# Pico_40Pin_Keyboard.net
KiCad netlist of a schematic drawn in EAGLE
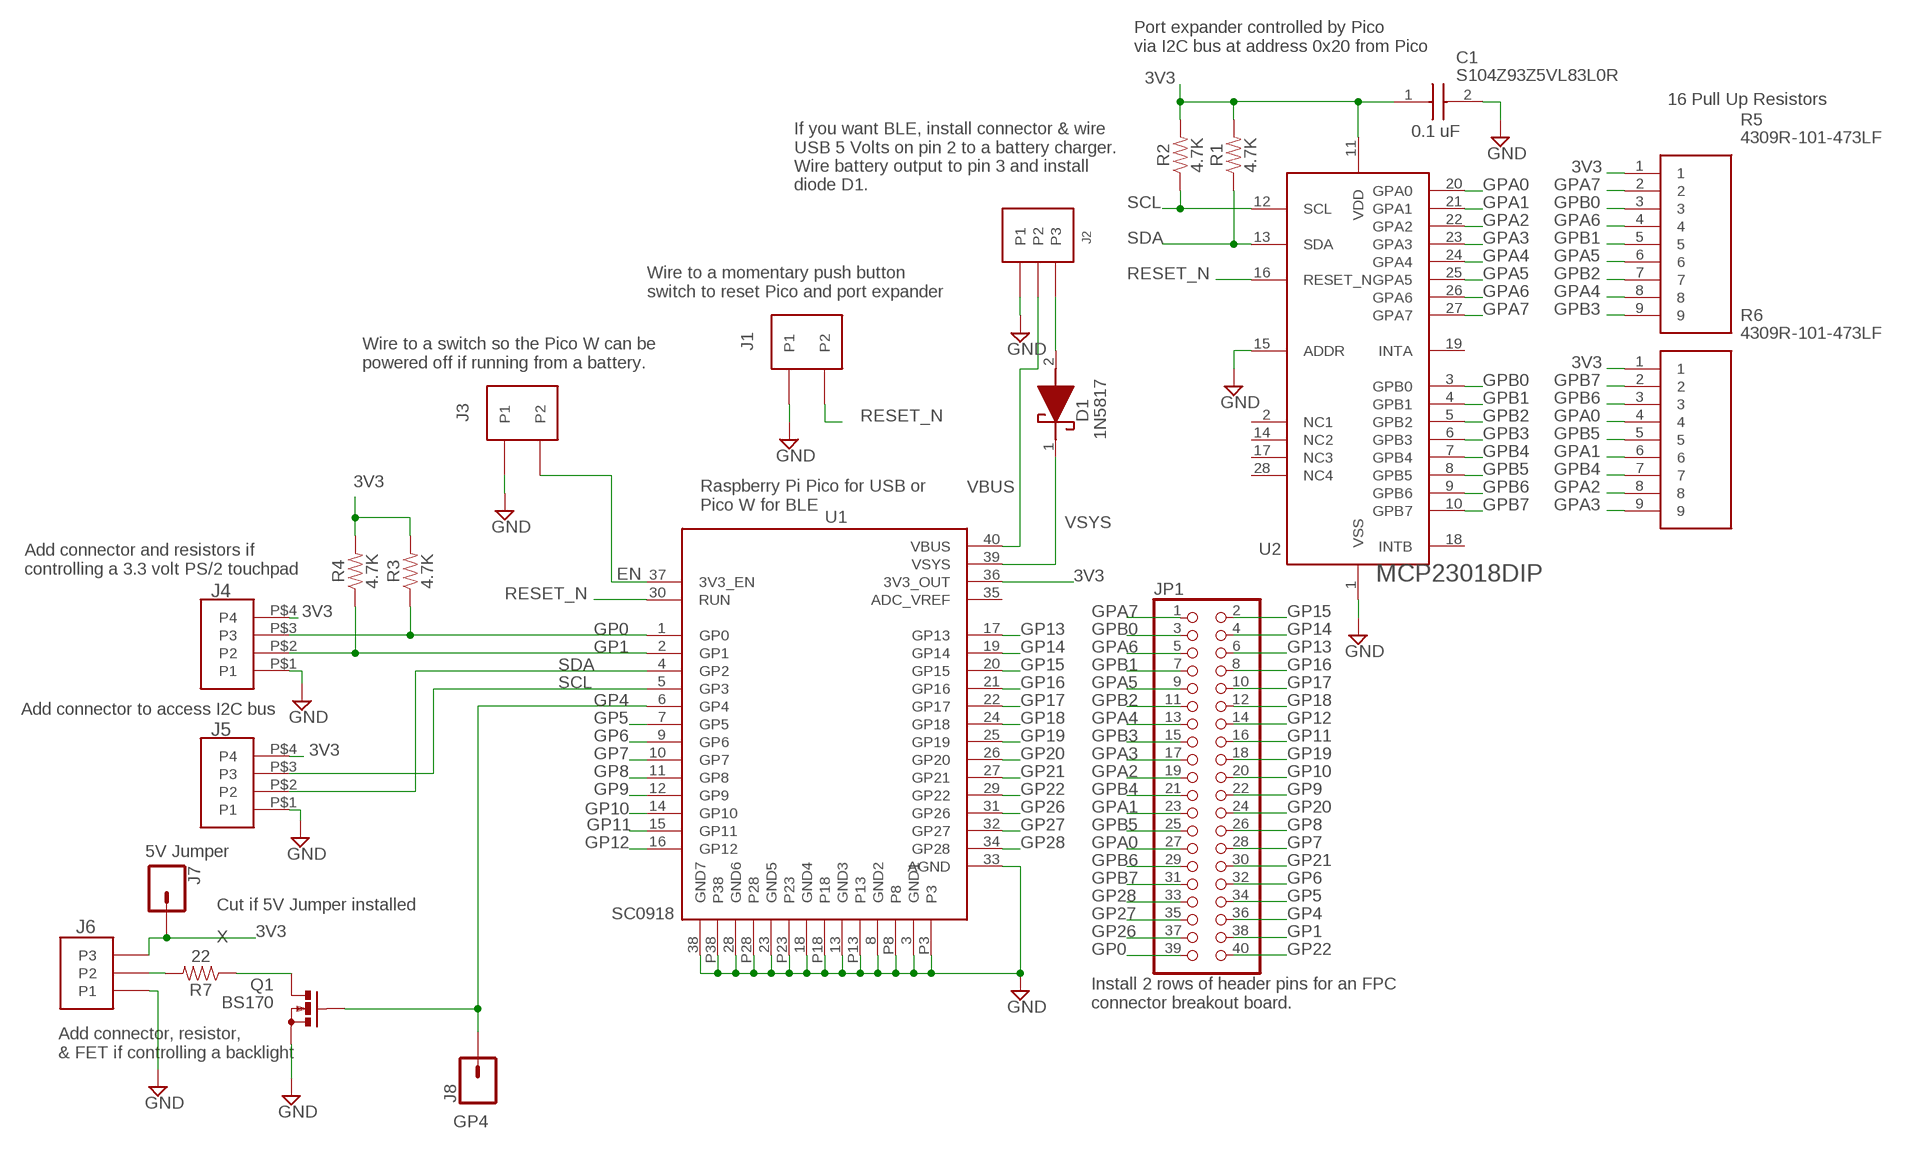
[diagram p0: schematic, sheet 1]

(export (version "E")
  (design (tool "Eeschema 10.0.6"))
  (components
    (comp (ref "C1")
      (value "S104Z93Z5VL83L0R")
      (footprint "eagle-import:S104Z93Z5VL83L0R")
      (fields (field (name "MOUSER_PART_NUMBER") "594-S104Z93Z5VL83L0R"))
      (libsource (lib "eagle-import") (part "S104Z93Z5VL83L0R"))
    )
    (comp (ref "D1")
      (value "1N5817")
      (footprint "eagle-import:DIOAD1410W86L470D235")
      (fields (field (name "MOUSER_PART_NUMBER") "821-1N5817"))
      (libsource (lib "eagle-import") (part "1N5817"))
    )
    (comp (ref "J1")
      (value "JST-PH-2PIN")
      (footprint "eagle-import:JST-PH-2PIN")
      (libsource (lib "eagle-import") (part "JST-PH-2PIN"))
    )
    (comp (ref "J2")
      (value "JST-PH-3PIN")
      (footprint "eagle-import:JST-PH-3PIN")
      (libsource (lib "eagle-import") (part "JST-PH-3PIN"))
    )
    (comp (ref "J3")
      (value "JST-PH-2PIN")
      (footprint "eagle-import:JST-PH-2PIN")
      (libsource (lib "eagle-import") (part "JST-PH-2PIN"))
    )
    (comp (ref "J4")
      (value "JST-PH-4PIN")
      (footprint "eagle-import:JST-PH-4PIN")
      (libsource (lib "eagle-import") (part "JST-PH-4PIN"))
    )
    (comp (ref "J5")
      (value "JST-PH-4PIN")
      (footprint "eagle-import:JST-PH-4PIN")
      (libsource (lib "eagle-import") (part "JST-PH-4PIN"))
    )
    (comp (ref "J6")
      (value "JST-PH-3PIN")
      (footprint "eagle-import:JST-PH-3PIN")
      (libsource (lib "eagle-import") (part "JST-PH-3PIN"))
    )
    (comp (ref "J7")
      (value "CONN_01")
      (footprint "eagle-import:1X01")
      (libsource (lib "eagle-import") (part "CONN_01"))
    )
    (comp (ref "J8")
      (value "CONN_01")
      (footprint "eagle-import:1X01")
      (libsource (lib "eagle-import") (part "CONN_01"))
    )
    (comp (ref "JP1")
      (value "PINHD-2X20")
      (footprint "eagle-import:2X20")
      (libsource (lib "eagle-import") (part "PINHD-2X20"))
    )
    (comp (ref "Q1")
      (value "BS170")
      (footprint "eagle-import:SOT54E")
      (libsource (lib "eagle-import") (part "BS170"))
    )
    (comp (ref "R1")
      (value "4.7K")
      (footprint "eagle-import:AXIAL-0.3")
      (libsource (lib "eagle-import") (part "RESISTOR_AXIAL"))
    )
    (comp (ref "R2")
      (value "4.7K")
      (footprint "eagle-import:AXIAL-0.3")
      (libsource (lib "eagle-import") (part "RESISTOR_AXIAL"))
    )
    (comp (ref "R3")
      (value "4.7K")
      (footprint "eagle-import:AXIAL-0.3")
      (libsource (lib "eagle-import") (part "RESISTOR_AXIAL"))
    )
    (comp (ref "R4")
      (value "4.7K")
      (footprint "eagle-import:AXIAL-0.3")
      (libsource (lib "eagle-import") (part "RESISTOR_AXIAL"))
    )
    (comp (ref "R5")
      (value "4309R-101-473LF")
      (footprint "eagle-import:4309R-101-473LF")
      (libsource (lib "eagle-import") (part "4309R-101-473LF"))
    )
    (comp (ref "R6")
      (value "4309R-101-473LF")
      (footprint "eagle-import:4309R-101-473LF")
      (libsource (lib "eagle-import") (part "4309R-101-473LF"))
    )
    (comp (ref "R7")
      (value "22")
      (footprint "eagle-import:AXIAL-0.3")
      (libsource (lib "eagle-import") (part "RESISTOR_AXIAL"))
    )
    (comp (ref "U1")
      (value "SC0918")
      (footprint "eagle-import:MODULE_SC0918")
      (fields (field (name "MF") "Raspberry Pi"))
      (libsource (lib "eagle-import") (part "SC0918"))
    )
    (comp (ref "U2")
      (value "MCP23018DIP")
      (footprint "eagle-import:MCP23018DIP")
      (libsource (lib "eagle-import") (part "MCP23018DIP"))
    )
  )
  (nets
    (net (code "1") (name "/3V3") (class "Default")
      (node (ref "C1") (pin "1") (pinfunction "1_1") (pintype "bidirectional"))
      (node (ref "J4") (pin "P$4") (pinfunction "P4_P$4") (pintype "bidirectional"))
      (node (ref "J5") (pin "P$4") (pinfunction "P4_P$4") (pintype "bidirectional"))
      (node (ref "J6") (pin "P$3") (pinfunction "P3_P$3") (pintype "bidirectional"))
      (node (ref "J7") (pin "1") (pinfunction "1_1") (pintype "passive"))
      (node (ref "R1") (pin "P$2") (pinfunction "2_P$2") (pintype "passive"))
      (node (ref "R2") (pin "P$2") (pinfunction "2_P$2") (pintype "passive"))
      (node (ref "R3") (pin "P$2") (pinfunction "2_P$2") (pintype "passive"))
      (node (ref "R4") (pin "P$2") (pinfunction "2_P$2") (pintype "passive"))
      (node (ref "R5") (pin "1") (pinfunction "1_1") (pintype "bidirectional"))
      (node (ref "R6") (pin "1") (pinfunction "1_1") (pintype "bidirectional"))
      (node (ref "U1") (pin "36") (pinfunction "3V3_OUT_36") (pintype "power_in"))
      (node (ref "U2") (pin "11") (pinfunction "VDD_11") (pintype "bidirectional"))
    )
    (net (code "2") (name "/ADC_VREF") (class "Default")
      (node (ref "U1") (pin "35") (pinfunction "ADC_VREF_35") (pintype "power_in"))
    )
    (net (code "3") (name "/EN") (class "Default")
      (node (ref "J3") (pin "P$2") (pinfunction "P2_P$2") (pintype "bidirectional"))
      (node (ref "U1") (pin "37") (pinfunction "3V3_EN_37") (pintype "input"))
    )
    (net (code "4") (name "/GP0") (class "Default")
      (node (ref "J4") (pin "P$3") (pinfunction "P3_P$3") (pintype "bidirectional"))
      (node (ref "JP1") (pin "39") (pinfunction "39_39") (pintype "passive"))
      (node (ref "R3") (pin "P$1") (pinfunction "1_P$1") (pintype "passive"))
      (node (ref "U1") (pin "1") (pinfunction "GP0_1") (pintype "bidirectional"))
    )
    (net (code "5") (name "/GP1") (class "Default")
      (node (ref "J4") (pin "P$2") (pinfunction "P2_P$2") (pintype "bidirectional"))
      (node (ref "JP1") (pin "38") (pinfunction "38_38") (pintype "passive"))
      (node (ref "R4") (pin "P$1") (pinfunction "1_P$1") (pintype "passive"))
      (node (ref "U1") (pin "2") (pinfunction "GP1_2") (pintype "bidirectional"))
    )
    (net (code "6") (name "/GP4") (class "Default")
      (node (ref "J8") (pin "1") (pinfunction "1_1") (pintype "passive"))
      (node (ref "JP1") (pin "36") (pinfunction "36_36") (pintype "passive"))
      (node (ref "Q1") (pin "G") (pinfunction "G_G") (pintype "passive"))
      (node (ref "U1") (pin "6") (pinfunction "GP4_6") (pintype "bidirectional"))
    )
    (net (code "7") (name "/GP5") (class "Default")
      (node (ref "JP1") (pin "34") (pinfunction "34_34") (pintype "passive"))
      (node (ref "U1") (pin "7") (pinfunction "GP5_7") (pintype "bidirectional"))
    )
    (net (code "8") (name "/GP6") (class "Default")
      (node (ref "JP1") (pin "32") (pinfunction "32_32") (pintype "passive"))
      (node (ref "U1") (pin "9") (pinfunction "GP6_9") (pintype "bidirectional"))
    )
    (net (code "9") (name "/GP7") (class "Default")
      (node (ref "JP1") (pin "28") (pinfunction "28_28") (pintype "passive"))
      (node (ref "U1") (pin "10") (pinfunction "GP7_10") (pintype "bidirectional"))
    )
    (net (code "10") (name "/GP8") (class "Default")
      (node (ref "JP1") (pin "26") (pinfunction "26_26") (pintype "passive"))
      (node (ref "U1") (pin "11") (pinfunction "GP8_11") (pintype "bidirectional"))
    )
    (net (code "11") (name "/GP9") (class "Default")
      (node (ref "JP1") (pin "22") (pinfunction "22_22") (pintype "passive"))
      (node (ref "U1") (pin "12") (pinfunction "GP9_12") (pintype "bidirectional"))
    )
    (net (code "12") (name "/GP10") (class "Default")
      (node (ref "JP1") (pin "20") (pinfunction "20_20") (pintype "passive"))
      (node (ref "U1") (pin "14") (pinfunction "GP10_14") (pintype "bidirectional"))
    )
    (net (code "13") (name "/GP11") (class "Default")
      (node (ref "JP1") (pin "16") (pinfunction "16_16") (pintype "passive"))
      (node (ref "U1") (pin "15") (pinfunction "GP11_15") (pintype "bidirectional"))
    )
    (net (code "14") (name "/GP12") (class "Default")
      (node (ref "JP1") (pin "14") (pinfunction "14_14") (pintype "passive"))
      (node (ref "U1") (pin "16") (pinfunction "GP12_16") (pintype "bidirectional"))
    )
    (net (code "15") (name "/GP13") (class "Default")
      (node (ref "JP1") (pin "6") (pinfunction "6_6") (pintype "passive"))
      (node (ref "U1") (pin "17") (pinfunction "GP13_17") (pintype "bidirectional"))
    )
    (net (code "16") (name "/GP14") (class "Default")
      (node (ref "JP1") (pin "4") (pinfunction "4_4") (pintype "passive"))
      (node (ref "U1") (pin "19") (pinfunction "GP14_19") (pintype "bidirectional"))
    )
    (net (code "17") (name "/GP15") (class "Default")
      (node (ref "JP1") (pin "2") (pinfunction "2_2") (pintype "passive"))
      (node (ref "U1") (pin "20") (pinfunction "GP15_20") (pintype "bidirectional"))
    )
    (net (code "18") (name "/GP16") (class "Default")
      (node (ref "JP1") (pin "8") (pinfunction "8_8") (pintype "passive"))
      (node (ref "U1") (pin "21") (pinfunction "GP16_21") (pintype "bidirectional"))
    )
    (net (code "19") (name "/GP17") (class "Default")
      (node (ref "JP1") (pin "10") (pinfunction "10_10") (pintype "passive"))
      (node (ref "U1") (pin "22") (pinfunction "GP17_22") (pintype "bidirectional"))
    )
    (net (code "20") (name "/GP18") (class "Default")
      (node (ref "JP1") (pin "12") (pinfunction "12_12") (pintype "passive"))
      (node (ref "U1") (pin "24") (pinfunction "GP18_24") (pintype "bidirectional"))
    )
    (net (code "21") (name "/GP19") (class "Default")
      (node (ref "JP1") (pin "18") (pinfunction "18_18") (pintype "passive"))
      (node (ref "U1") (pin "25") (pinfunction "GP19_25") (pintype "bidirectional"))
    )
    (net (code "22") (name "/GP20") (class "Default")
      (node (ref "JP1") (pin "24") (pinfunction "24_24") (pintype "passive"))
      (node (ref "U1") (pin "26") (pinfunction "GP20_26") (pintype "bidirectional"))
    )
    (net (code "23") (name "/GP21") (class "Default")
      (node (ref "JP1") (pin "30") (pinfunction "30_30") (pintype "passive"))
      (node (ref "U1") (pin "27") (pinfunction "GP21_27") (pintype "bidirectional"))
    )
    (net (code "24") (name "/GP22") (class "Default")
      (node (ref "JP1") (pin "40") (pinfunction "40_40") (pintype "passive"))
      (node (ref "U1") (pin "29") (pinfunction "GP22_29") (pintype "bidirectional"))
    )
    (net (code "25") (name "/GP26") (class "Default")
      (node (ref "JP1") (pin "37") (pinfunction "37_37") (pintype "passive"))
      (node (ref "U1") (pin "31") (pinfunction "GP26_31") (pintype "bidirectional"))
    )
    (net (code "26") (name "/GP27") (class "Default")
      (node (ref "JP1") (pin "35") (pinfunction "35_35") (pintype "passive"))
      (node (ref "U1") (pin "32") (pinfunction "GP27_32") (pintype "bidirectional"))
    )
    (net (code "27") (name "/GP28") (class "Default")
      (node (ref "JP1") (pin "33") (pinfunction "33_33") (pintype "passive"))
      (node (ref "U1") (pin "34") (pinfunction "GP28_34") (pintype "bidirectional"))
    )
    (net (code "28") (name "/GPA0") (class "Default")
      (node (ref "JP1") (pin "27") (pinfunction "27_27") (pintype "passive"))
      (node (ref "R6") (pin "4") (pinfunction "4_4") (pintype "bidirectional"))
      (node (ref "U2") (pin "20") (pinfunction "GPA0_20") (pintype "bidirectional"))
    )
    (net (code "29") (name "/GPA1") (class "Default")
      (node (ref "JP1") (pin "23") (pinfunction "23_23") (pintype "passive"))
      (node (ref "R6") (pin "6") (pinfunction "6_6") (pintype "bidirectional"))
      (node (ref "U2") (pin "21") (pinfunction "GPA1_21") (pintype "bidirectional"))
    )
    (net (code "30") (name "/GPA2") (class "Default")
      (node (ref "JP1") (pin "19") (pinfunction "19_19") (pintype "passive"))
      (node (ref "R6") (pin "8") (pinfunction "8_8") (pintype "bidirectional"))
      (node (ref "U2") (pin "22") (pinfunction "GPA2_22") (pintype "bidirectional"))
    )
    (net (code "31") (name "/GPA3") (class "Default")
      (node (ref "JP1") (pin "17") (pinfunction "17_17") (pintype "passive"))
      (node (ref "R6") (pin "9") (pinfunction "9_9") (pintype "bidirectional"))
      (node (ref "U2") (pin "23") (pinfunction "GPA3_23") (pintype "bidirectional"))
    )
    (net (code "32") (name "/GPA4") (class "Default")
      (node (ref "JP1") (pin "13") (pinfunction "13_13") (pintype "passive"))
      (node (ref "R5") (pin "8") (pinfunction "8_8") (pintype "bidirectional"))
      (node (ref "U2") (pin "24") (pinfunction "GPA4_24") (pintype "bidirectional"))
    )
    (net (code "33") (name "/GPA5") (class "Default")
      (node (ref "JP1") (pin "9") (pinfunction "9_9") (pintype "passive"))
      (node (ref "R5") (pin "6") (pinfunction "6_6") (pintype "bidirectional"))
      (node (ref "U2") (pin "25") (pinfunction "GPA5_25") (pintype "bidirectional"))
    )
    (net (code "34") (name "/GPA6") (class "Default")
      (node (ref "JP1") (pin "5") (pinfunction "5_5") (pintype "passive"))
      (node (ref "R5") (pin "4") (pinfunction "4_4") (pintype "bidirectional"))
      (node (ref "U2") (pin "26") (pinfunction "GPA6_26") (pintype "bidirectional"))
    )
    (net (code "35") (name "/GPA7") (class "Default")
      (node (ref "JP1") (pin "1") (pinfunction "1_1") (pintype "passive"))
      (node (ref "R5") (pin "2") (pinfunction "2_2") (pintype "bidirectional"))
      (node (ref "U2") (pin "27") (pinfunction "GPA7_27") (pintype "bidirectional"))
    )
    (net (code "36") (name "/GPB0") (class "Default")
      (node (ref "JP1") (pin "3") (pinfunction "3_3") (pintype "passive"))
      (node (ref "R5") (pin "3") (pinfunction "3_3") (pintype "bidirectional"))
      (node (ref "U2") (pin "3") (pinfunction "GPB0_3") (pintype "bidirectional"))
    )
    (net (code "37") (name "/GPB1") (class "Default")
      (node (ref "JP1") (pin "7") (pinfunction "7_7") (pintype "passive"))
      (node (ref "R5") (pin "5") (pinfunction "5_5") (pintype "bidirectional"))
      (node (ref "U2") (pin "4") (pinfunction "GPB1_4") (pintype "bidirectional"))
    )
    (net (code "38") (name "/GPB2") (class "Default")
      (node (ref "JP1") (pin "11") (pinfunction "11_11") (pintype "passive"))
      (node (ref "R5") (pin "7") (pinfunction "7_7") (pintype "bidirectional"))
      (node (ref "U2") (pin "5") (pinfunction "GPB2_5") (pintype "bidirectional"))
    )
    (net (code "39") (name "/GPB3") (class "Default")
      (node (ref "JP1") (pin "15") (pinfunction "15_15") (pintype "passive"))
      (node (ref "R5") (pin "9") (pinfunction "9_9") (pintype "bidirectional"))
      (node (ref "U2") (pin "6") (pinfunction "GPB3_6") (pintype "bidirectional"))
    )
    (net (code "40") (name "/GPB4") (class "Default")
      (node (ref "JP1") (pin "21") (pinfunction "21_21") (pintype "passive"))
      (node (ref "R6") (pin "7") (pinfunction "7_7") (pintype "bidirectional"))
      (node (ref "U2") (pin "7") (pinfunction "GPB4_7") (pintype "bidirectional"))
    )
    (net (code "41") (name "/GPB5") (class "Default")
      (node (ref "JP1") (pin "25") (pinfunction "25_25") (pintype "passive"))
      (node (ref "R6") (pin "5") (pinfunction "5_5") (pintype "bidirectional"))
      (node (ref "U2") (pin "8") (pinfunction "GPB5_8") (pintype "bidirectional"))
    )
    (net (code "42") (name "/GPB6") (class "Default")
      (node (ref "JP1") (pin "29") (pinfunction "29_29") (pintype "passive"))
      (node (ref "R6") (pin "3") (pinfunction "3_3") (pintype "bidirectional"))
      (node (ref "U2") (pin "9") (pinfunction "GPB6_9") (pintype "bidirectional"))
    )
    (net (code "43") (name "/GPB7") (class "Default")
      (node (ref "JP1") (pin "31") (pinfunction "31_31") (pintype "passive"))
      (node (ref "R6") (pin "2") (pinfunction "2_2") (pintype "bidirectional"))
      (node (ref "U2") (pin "10") (pinfunction "GPB7_10") (pintype "bidirectional"))
    )
    (net (code "44") (name "/RESET_N") (class "Default")
      (node (ref "J1") (pin "P$2") (pinfunction "P2_P$2") (pintype "bidirectional"))
      (node (ref "U1") (pin "30") (pinfunction "RUN_30") (pintype "input"))
      (node (ref "U2") (pin "16") (pinfunction "RESET_N_16") (pintype "bidirectional"))
    )
    (net (code "45") (name "/SCL") (class "Default")
      (node (ref "J5") (pin "P$3") (pinfunction "P3_P$3") (pintype "bidirectional"))
      (node (ref "R2") (pin "P$1") (pinfunction "1_P$1") (pintype "passive"))
      (node (ref "U1") (pin "5") (pinfunction "GP3_5") (pintype "bidirectional"))
      (node (ref "U2") (pin "12") (pinfunction "SCL_12") (pintype "bidirectional"))
    )
    (net (code "46") (name "/SDA") (class "Default")
      (node (ref "J5") (pin "P$2") (pinfunction "P2_P$2") (pintype "bidirectional"))
      (node (ref "R1") (pin "P$1") (pinfunction "1_P$1") (pintype "passive"))
      (node (ref "U1") (pin "4") (pinfunction "GP2_4") (pintype "bidirectional"))
      (node (ref "U2") (pin "13") (pinfunction "SDA_13") (pintype "bidirectional"))
    )
    (net (code "47") (name "/VBUS") (class "Default")
      (node (ref "J2") (pin "P$2") (pinfunction "P2_P$2") (pintype "bidirectional"))
      (node (ref "U1") (pin "40") (pinfunction "VBUS_40") (pintype "power_in"))
    )
    (net (code "48") (name "/VSYS") (class "Default")
      (node (ref "D1") (pin "1") (pinfunction "K_1") (pintype "bidirectional"))
      (node (ref "U1") (pin "39") (pinfunction "VSYS_39") (pintype "power_in"))
    )
    (net (code "49") (name "GND") (class "Default")
      (node (ref "C1") (pin "2") (pinfunction "2_2") (pintype "bidirectional"))
      (node (ref "J1") (pin "P$1") (pinfunction "P1_P$1") (pintype "bidirectional"))
      (node (ref "J2") (pin "P$1") (pinfunction "P1_P$1") (pintype "bidirectional"))
      (node (ref "J3") (pin "P$1") (pinfunction "P1_P$1") (pintype "bidirectional"))
      (node (ref "J4") (pin "P$1") (pinfunction "P1_P$1") (pintype "bidirectional"))
      (node (ref "J5") (pin "P$1") (pinfunction "P1_P$1") (pintype "bidirectional"))
      (node (ref "J6") (pin "P$1") (pinfunction "P1_P$1") (pintype "bidirectional"))
      (node (ref "Q1") (pin "S") (pinfunction "S_S") (pintype "passive"))
      (node (ref "U1") (pin "13") (pinfunction "GND3_13") (pintype "power_in"))
      (node (ref "U1") (pin "18") (pinfunction "GND4_18") (pintype "power_in"))
      (node (ref "U1") (pin "23") (pinfunction "GND5_23") (pintype "power_in"))
      (node (ref "U1") (pin "28") (pinfunction "GND6_28") (pintype "power_in"))
      (node (ref "U1") (pin "3") (pinfunction "GND1_3") (pintype "power_in"))
      (node (ref "U1") (pin "33") (pinfunction "AGND_33") (pintype "power_in"))
      (node (ref "U1") (pin "38") (pinfunction "GND7_38") (pintype "power_in"))
      (node (ref "U1") (pin "8") (pinfunction "GND2_8") (pintype "power_in"))
      (node (ref "U1") (pin "P13") (pinfunction "P13_P13") (pintype "power_in"))
      (node (ref "U1") (pin "P18") (pinfunction "P18_P18") (pintype "power_in"))
      (node (ref "U1") (pin "P23") (pinfunction "P23_P23") (pintype "power_in"))
      (node (ref "U1") (pin "P28") (pinfunction "P28_P28") (pintype "power_in"))
      (node (ref "U1") (pin "P3") (pinfunction "P3_P3") (pintype "power_in"))
      (node (ref "U1") (pin "P38") (pinfunction "P38_P38") (pintype "power_in"))
      (node (ref "U1") (pin "P8") (pinfunction "P8_P8") (pintype "power_in"))
      (node (ref "U2") (pin "1") (pinfunction "VSS_1") (pintype "bidirectional"))
      (node (ref "U2") (pin "15") (pinfunction "ADDR_15") (pintype "bidirectional"))
    )
    (net (code "50") (name "Net-(D1-A)") (class "Default")
      (node (ref "D1") (pin "2") (pinfunction "A_2") (pintype "bidirectional"))
      (node (ref "J2") (pin "P$3") (pinfunction "P3_P$3") (pintype "bidirectional"))
    )
    (net (code "51") (name "Net-(J6-P2)") (class "Default")
      (node (ref "J6") (pin "P$2") (pinfunction "P2_P$2") (pintype "bidirectional"))
      (node (ref "R7") (pin "P$2") (pinfunction "2_P$2") (pintype "passive"))
    )
    (net (code "52") (name "Net-(R7-1)") (class "Default")
      (node (ref "Q1") (pin "D") (pinfunction "D_D") (pintype "passive"))
      (node (ref "R7") (pin "P$1") (pinfunction "1_P$1") (pintype "passive"))
    )
    (net (code "53") (name "unconnected-(U2-INTA-Pad19)") (class "Default")
      (node (ref "U2") (pin "19") (pinfunction "INTA_19") (pintype "bidirectional"))
    )
    (net (code "54") (name "unconnected-(U2-INTB-Pad18)") (class "Default")
      (node (ref "U2") (pin "18") (pinfunction "INTB_18") (pintype "bidirectional"))
    )
    (net (code "55") (name "unconnected-(U2-NC1-Pad2)") (class "Default")
      (node (ref "U2") (pin "2") (pinfunction "NC1_2") (pintype "bidirectional"))
    )
    (net (code "56") (name "unconnected-(U2-NC2-Pad14)") (class "Default")
      (node (ref "U2") (pin "14") (pinfunction "NC2_14") (pintype "bidirectional"))
    )
    (net (code "57") (name "unconnected-(U2-NC3-Pad17)") (class "Default")
      (node (ref "U2") (pin "17") (pinfunction "NC3_17") (pintype "bidirectional"))
    )
    (net (code "58") (name "unconnected-(U2-NC4-Pad28)") (class "Default")
      (node (ref "U2") (pin "28") (pinfunction "NC4_28") (pintype "bidirectional"))
    )
  )
)
